# rainGauge.net
KiCad netlist of a schematic drawn in EAGLE
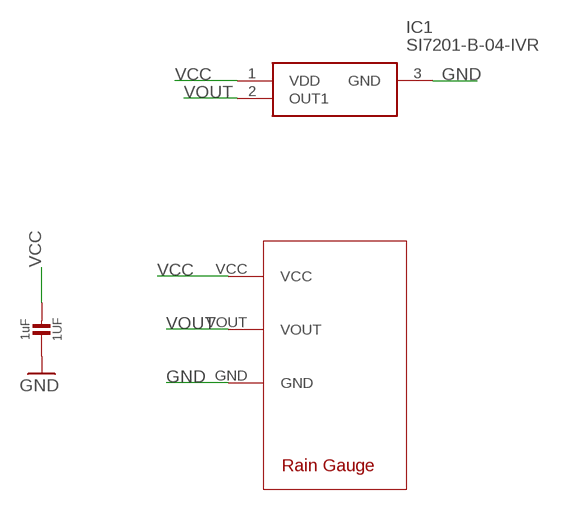
[diagram p0: schematic, sheet 1]

(export (version "E")
  (design (tool "Eeschema 10.0.6"))
  (components
    (comp (ref "1UF")
      (value "1uF")
      (footprint "eagle-import:0805-NO")
      (libsource (lib "eagle-import") (part "CAP_CERAMIC0805-NOOUTLINE"))
    )
    (comp (ref "IC1")
      (value "SI7201-B-04-IVR")
      (footprint "eagle-import:SOT95P275X125-3N")
      (fields
        (field (name "MANUFACTURER_PART_NUMBER") "Si7201-B-04-IVR")
        (field (name "RS_PART_NUMBER") "1446543")
      )
      (libsource (lib "eagle-import") (part "SI7201-B-04-IVR"))
    )
    (comp (ref "U$1")
      (value "RAINGAUGERAINPAD")
      (footprint "eagle-import:RAINGAUGE")
      (libsource (lib "eagle-import") (part "RAINGAUGERAINPAD"))
    )
  )
  (nets
    (net (code "1") (name "/VCC") (class "Default")
      (node (ref "1UF") (pin "2") (pinfunction "2_2") (pintype "passive"))
      (node (ref "IC1") (pin "1") (pinfunction "VDD_1") (pintype "bidirectional"))
      (node (ref "U$1") (pin "VCC") (pinfunction "VCC_VCC") (pintype "bidirectional"))
    )
    (net (code "2") (name "/VOUT") (class "Default")
      (node (ref "IC1") (pin "2") (pinfunction "OUT1_2") (pintype "bidirectional"))
      (node (ref "U$1") (pin "VOUT") (pinfunction "VOUT_VOUT") (pintype "bidirectional"))
    )
    (net (code "3") (name "GND") (class "Default")
      (node (ref "1UF") (pin "1") (pinfunction "1_1") (pintype "passive"))
      (node (ref "IC1") (pin "3") (pinfunction "GND_3") (pintype "bidirectional"))
      (node (ref "U$1") (pin "GND") (pinfunction "GND_GND") (pintype "bidirectional"))
    )
  )
)
